# LED_SHEET.net
KiCad netlist of a schematic drawn in Altium Designer
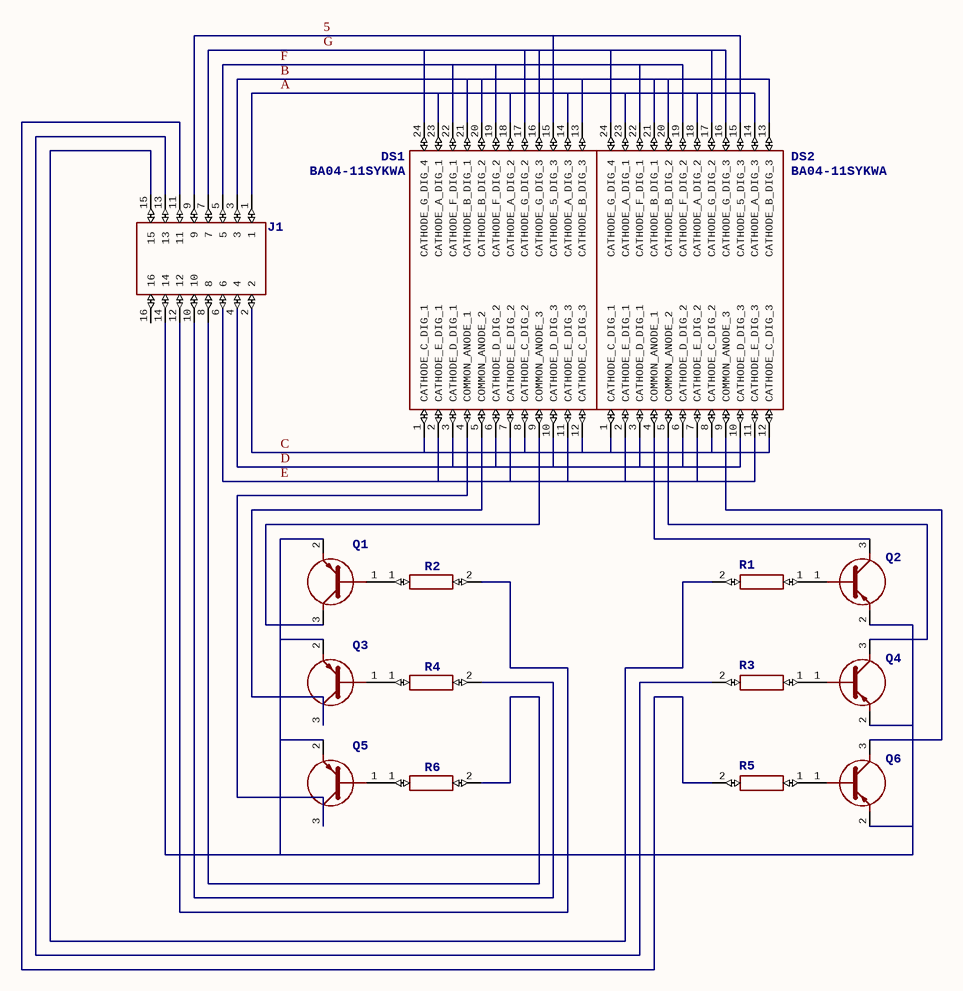
[diagram p0: LED_SHEET.SchDoc]

(export (version "E")
  (design (tool "Eeschema 10.0.6"))
  (components
    (comp (ref "DS1")
      (value "BA04-11SYKWA")
      (footprint "DIPS1270W70P254L3020H725Q24N")
      (libsource (lib "877-0833") (part "BA04-11SYKWA"))
    )
    (comp (ref "DS2")
      (value "BA04-11SYKWA")
      (footprint "DIPS1270W70P254L3020H725Q24N")
      (libsource (lib "877-0833") (part "BA04-11SYKWA"))
    )
    (comp (ref "J1")
      (value "~")
      (footprint "SHDR16W64P254_2X8_2790X860X930")
      (fields (field (name "MANUFACTURER_PART_NUMBER") "6257268"))
      (libsource (lib "625-7268") (part "6257268"))
    )
    (comp (ref "Q1")
      (value "~")
      (footprint "SOT95P230X110-3N")
      (fields
        (field (name "MANUFACTURER_PART_NUMBER") "BC857,215")
        (field (name "MOUSER_PART_NUMBER") "771-BC857215")
      )
      (libsource (lib "484-5100") (part "BC857,215"))
    )
    (comp (ref "Q2")
      (value "~")
      (footprint "SOT95P230X110-3N")
      (fields
        (field (name "MANUFACTURER_PART_NUMBER") "BC857,215")
        (field (name "MOUSER_PART_NUMBER") "771-BC857215")
      )
      (libsource (lib "484-5100") (part "BC857,215"))
    )
    (comp (ref "Q3")
      (value "~")
      (footprint "SOT95P230X110-3N")
      (fields
        (field (name "MANUFACTURER_PART_NUMBER") "BC857,215")
        (field (name "MOUSER_PART_NUMBER") "771-BC857215")
      )
      (libsource (lib "484-5100") (part "BC857,215"))
    )
    (comp (ref "Q4")
      (value "~")
      (footprint "SOT95P230X110-3N")
      (fields
        (field (name "MANUFACTURER_PART_NUMBER") "BC857,215")
        (field (name "MOUSER_PART_NUMBER") "771-BC857215")
      )
      (libsource (lib "484-5100") (part "BC857,215"))
    )
    (comp (ref "Q5")
      (value "~")
      (footprint "SOT95P230X110-3N")
      (fields
        (field (name "MANUFACTURER_PART_NUMBER") "BC857,215")
        (field (name "MOUSER_PART_NUMBER") "771-BC857215")
      )
      (libsource (lib "484-5100") (part "BC857,215"))
    )
    (comp (ref "Q6")
      (value "~")
      (footprint "SOT95P230X110-3N")
      (fields
        (field (name "MANUFACTURER_PART_NUMBER") "BC857,215")
        (field (name "MOUSER_PART_NUMBER") "771-BC857215")
      )
      (libsource (lib "484-5100") (part "BC857,215"))
    )
    (comp (ref "R1")
      (value "~")
      (footprint "RESC3116X65N")
      (fields
        (field (name "MANUFACTURER_PART_NUMBER") "CRG1206F150R")
        (field (name "MOUSER_PART_NUMBER") "279-CRG1206F150R")
      )
      (libsource (lib "223-2142") (part "CRG1206F150R"))
    )
    (comp (ref "R2")
      (value "~")
      (footprint "RESC3116X65N")
      (fields
        (field (name "MANUFACTURER_PART_NUMBER") "CRG1206F150R")
        (field (name "MOUSER_PART_NUMBER") "279-CRG1206F150R")
      )
      (libsource (lib "223-2142") (part "CRG1206F150R"))
    )
    (comp (ref "R3")
      (value "~")
      (footprint "RESC3116X65N")
      (fields
        (field (name "MANUFACTURER_PART_NUMBER") "CRG1206F150R")
        (field (name "MOUSER_PART_NUMBER") "279-CRG1206F150R")
      )
      (libsource (lib "223-2142") (part "CRG1206F150R"))
    )
    (comp (ref "R4")
      (value "~")
      (footprint "RESC3116X65N")
      (fields
        (field (name "MANUFACTURER_PART_NUMBER") "CRG1206F150R")
        (field (name "MOUSER_PART_NUMBER") "279-CRG1206F150R")
      )
      (libsource (lib "223-2142") (part "CRG1206F150R"))
    )
    (comp (ref "R5")
      (value "~")
      (footprint "RESC3116X65N")
      (fields
        (field (name "MANUFACTURER_PART_NUMBER") "CRG1206F150R")
        (field (name "MOUSER_PART_NUMBER") "279-CRG1206F150R")
      )
      (libsource (lib "223-2142") (part "CRG1206F150R"))
    )
    (comp (ref "R6")
      (value "~")
      (footprint "RESC3116X65N")
      (fields
        (field (name "MANUFACTURER_PART_NUMBER") "CRG1206F150R")
        (field (name "MOUSER_PART_NUMBER") "279-CRG1206F150R")
      )
      (libsource (lib "223-2142") (part "CRG1206F150R"))
    )
  )
  (nets
    (net (code "1") (name "/5") (class "Default")
      (node (ref "DS1") (pin "15") (pinfunction "CATHODE_5_DIG_3_15") (pintype "bidirectional"))
      (node (ref "DS2") (pin "15") (pinfunction "CATHODE_5_DIG_3_15") (pintype "bidirectional"))
      (node (ref "J1") (pin "9") (pinfunction "9_9") (pintype "bidirectional"))
    )
    (net (code "2") (name "/A") (class "Default")
      (node (ref "DS1") (pin "14") (pinfunction "CATHODE_A_DIG_3_14") (pintype "bidirectional"))
      (node (ref "DS1") (pin "18") (pinfunction "CATHODE_A_DIG_2_18") (pintype "bidirectional"))
      (node (ref "DS1") (pin "23") (pinfunction "CATHODE_A_DIG_1_23") (pintype "bidirectional"))
      (node (ref "DS2") (pin "14") (pinfunction "CATHODE_A_DIG_3_14") (pintype "bidirectional"))
      (node (ref "DS2") (pin "18") (pinfunction "CATHODE_A_DIG_2_18") (pintype "bidirectional"))
      (node (ref "DS2") (pin "23") (pinfunction "CATHODE_A_DIG_1_23") (pintype "bidirectional"))
      (node (ref "J1") (pin "1") (pinfunction "1_1") (pintype "bidirectional"))
    )
    (net (code "3") (name "/B") (class "Default")
      (node (ref "DS1") (pin "13") (pinfunction "CATHODE_B_DIG_3_13") (pintype "bidirectional"))
      (node (ref "DS1") (pin "20") (pinfunction "CATHODE_B_DIG_2_20") (pintype "bidirectional"))
      (node (ref "DS1") (pin "21") (pinfunction "CATHODE_B_DIG_1_21") (pintype "bidirectional"))
      (node (ref "DS2") (pin "13") (pinfunction "CATHODE_B_DIG_3_13") (pintype "bidirectional"))
      (node (ref "DS2") (pin "20") (pinfunction "CATHODE_B_DIG_2_20") (pintype "bidirectional"))
      (node (ref "DS2") (pin "21") (pinfunction "CATHODE_B_DIG_1_21") (pintype "bidirectional"))
      (node (ref "J1") (pin "3") (pinfunction "3_3") (pintype "bidirectional"))
    )
    (net (code "4") (name "/C") (class "Default")
      (node (ref "DS1") (pin "1") (pinfunction "CATHODE_C_DIG_1_1") (pintype "bidirectional"))
      (node (ref "DS1") (pin "12") (pinfunction "CATHODE_C_DIG_3_12") (pintype "bidirectional"))
      (node (ref "DS1") (pin "8") (pinfunction "CATHODE_C_DIG_2_8") (pintype "bidirectional"))
      (node (ref "DS2") (pin "1") (pinfunction "CATHODE_C_DIG_1_1") (pintype "bidirectional"))
      (node (ref "DS2") (pin "12") (pinfunction "CATHODE_C_DIG_3_12") (pintype "bidirectional"))
      (node (ref "DS2") (pin "8") (pinfunction "CATHODE_C_DIG_2_8") (pintype "bidirectional"))
      (node (ref "J1") (pin "2") (pinfunction "2_2") (pintype "bidirectional"))
    )
    (net (code "5") (name "/D") (class "Default")
      (node (ref "DS1") (pin "10") (pinfunction "CATHODE_D_DIG_3_10") (pintype "bidirectional"))
      (node (ref "DS1") (pin "3") (pinfunction "CATHODE_D_DIG_1_3") (pintype "bidirectional"))
      (node (ref "DS1") (pin "6") (pinfunction "CATHODE_D_DIG_2_6") (pintype "bidirectional"))
      (node (ref "DS2") (pin "10") (pinfunction "CATHODE_D_DIG_3_10") (pintype "bidirectional"))
      (node (ref "DS2") (pin "3") (pinfunction "CATHODE_D_DIG_1_3") (pintype "bidirectional"))
      (node (ref "DS2") (pin "6") (pinfunction "CATHODE_D_DIG_2_6") (pintype "bidirectional"))
      (node (ref "J1") (pin "4") (pinfunction "4_4") (pintype "bidirectional"))
    )
    (net (code "6") (name "/E") (class "Default")
      (node (ref "DS1") (pin "11") (pinfunction "CATHODE_E_DIG_3_11") (pintype "bidirectional"))
      (node (ref "DS1") (pin "2") (pinfunction "CATHODE_E_DIG_1_2") (pintype "bidirectional"))
      (node (ref "DS1") (pin "7") (pinfunction "CATHODE_E_DIG_2_7") (pintype "bidirectional"))
      (node (ref "DS2") (pin "11") (pinfunction "CATHODE_E_DIG_3_11") (pintype "bidirectional"))
      (node (ref "DS2") (pin "2") (pinfunction "CATHODE_E_DIG_1_2") (pintype "bidirectional"))
      (node (ref "DS2") (pin "7") (pinfunction "CATHODE_E_DIG_2_7") (pintype "bidirectional"))
      (node (ref "J1") (pin "6") (pinfunction "6_6") (pintype "bidirectional"))
    )
    (net (code "7") (name "/F") (class "Default")
      (node (ref "DS1") (pin "19") (pinfunction "CATHODE_F_DIG_2_19") (pintype "bidirectional"))
      (node (ref "DS1") (pin "22") (pinfunction "CATHODE_F_DIG_1_22") (pintype "bidirectional"))
      (node (ref "DS2") (pin "19") (pinfunction "CATHODE_F_DIG_2_19") (pintype "bidirectional"))
      (node (ref "DS2") (pin "22") (pinfunction "CATHODE_F_DIG_1_22") (pintype "bidirectional"))
      (node (ref "J1") (pin "5") (pinfunction "5_5") (pintype "bidirectional"))
    )
    (net (code "8") (name "/G") (class "Default")
      (node (ref "DS1") (pin "16") (pinfunction "CATHODE_G_DIG_3_16") (pintype "bidirectional"))
      (node (ref "DS1") (pin "17") (pinfunction "CATHODE_G_DIG_2_17") (pintype "bidirectional"))
      (node (ref "DS1") (pin "24") (pinfunction "CATHODE_G_DIG_4_24") (pintype "bidirectional"))
      (node (ref "DS2") (pin "16") (pinfunction "CATHODE_G_DIG_3_16") (pintype "bidirectional"))
      (node (ref "DS2") (pin "17") (pinfunction "CATHODE_G_DIG_2_17") (pintype "bidirectional"))
      (node (ref "DS2") (pin "24") (pinfunction "CATHODE_G_DIG_4_24") (pintype "bidirectional"))
      (node (ref "J1") (pin "7") (pinfunction "7_7") (pintype "bidirectional"))
    )
    (net (code "9") (name "Net-(DS1-COMMON_ANODE_1)") (class "Default")
      (node (ref "DS1") (pin "4") (pinfunction "COMMON_ANODE_1_4") (pintype "bidirectional"))
      (node (ref "Q5") (pin "3") (pinfunction "C_3") (pintype "bidirectional"))
    )
    (net (code "10") (name "Net-(DS1-COMMON_ANODE_2)") (class "Default")
      (node (ref "DS1") (pin "5") (pinfunction "COMMON_ANODE_2_5") (pintype "bidirectional"))
      (node (ref "Q3") (pin "3") (pinfunction "C_3") (pintype "bidirectional"))
    )
    (net (code "11") (name "Net-(DS1-COMMON_ANODE_3)") (class "Default")
      (node (ref "DS1") (pin "9") (pinfunction "COMMON_ANODE_3_9") (pintype "bidirectional"))
      (node (ref "Q1") (pin "3") (pinfunction "C_3") (pintype "bidirectional"))
    )
    (net (code "12") (name "Net-(DS2-COMMON_ANODE_1)") (class "Default")
      (node (ref "DS2") (pin "4") (pinfunction "COMMON_ANODE_1_4") (pintype "bidirectional"))
      (node (ref "Q2") (pin "3") (pinfunction "C_3") (pintype "bidirectional"))
    )
    (net (code "13") (name "Net-(DS2-COMMON_ANODE_2)") (class "Default")
      (node (ref "DS2") (pin "5") (pinfunction "COMMON_ANODE_2_5") (pintype "bidirectional"))
      (node (ref "Q4") (pin "3") (pinfunction "C_3") (pintype "bidirectional"))
    )
    (net (code "14") (name "Net-(DS2-COMMON_ANODE_3)") (class "Default")
      (node (ref "DS2") (pin "9") (pinfunction "COMMON_ANODE_3_9") (pintype "bidirectional"))
      (node (ref "Q6") (pin "3") (pinfunction "C_3") (pintype "bidirectional"))
    )
    (net (code "15") (name "Net-(J1-Pad8)") (class "Default")
      (node (ref "J1") (pin "8") (pinfunction "8_8") (pintype "bidirectional"))
      (node (ref "R6") (pin "2") (pinfunction "2_2") (pintype "bidirectional"))
    )
    (net (code "16") (name "Net-(J1-Pad10)") (class "Default")
      (node (ref "J1") (pin "10") (pinfunction "10_10") (pintype "bidirectional"))
      (node (ref "R4") (pin "2") (pinfunction "2_2") (pintype "bidirectional"))
    )
    (net (code "17") (name "Net-(J1-Pad11)") (class "Default")
      (node (ref "J1") (pin "11") (pinfunction "11_11") (pintype "bidirectional"))
      (node (ref "R5") (pin "2") (pinfunction "2_2") (pintype "bidirectional"))
    )
    (net (code "18") (name "Net-(J1-Pad12)") (class "Default")
      (node (ref "J1") (pin "12") (pinfunction "12_12") (pintype "bidirectional"))
      (node (ref "R2") (pin "2") (pinfunction "2_2") (pintype "bidirectional"))
    )
    (net (code "19") (name "Net-(J1-Pad13)") (class "Default")
      (node (ref "J1") (pin "13") (pinfunction "13_13") (pintype "bidirectional"))
      (node (ref "R3") (pin "2") (pinfunction "2_2") (pintype "bidirectional"))
    )
    (net (code "20") (name "Net-(J1-Pad15)") (class "Default")
      (node (ref "J1") (pin "15") (pinfunction "15_15") (pintype "bidirectional"))
      (node (ref "R1") (pin "2") (pinfunction "2_2") (pintype "bidirectional"))
    )
    (net (code "21") (name "Net-(Q1-B)") (class "Default")
      (node (ref "Q1") (pin "1") (pinfunction "B_1") (pintype "bidirectional"))
      (node (ref "R2") (pin "1") (pinfunction "1_1") (pintype "bidirectional"))
    )
    (net (code "22") (name "Net-(Q1-E)") (class "Default")
      (node (ref "J1") (pin "14") (pinfunction "14_14") (pintype "bidirectional"))
      (node (ref "Q1") (pin "2") (pinfunction "E_2") (pintype "bidirectional"))
      (node (ref "Q2") (pin "2") (pinfunction "E_2") (pintype "bidirectional"))
      (node (ref "Q3") (pin "2") (pinfunction "E_2") (pintype "bidirectional"))
      (node (ref "Q4") (pin "2") (pinfunction "E_2") (pintype "bidirectional"))
      (node (ref "Q5") (pin "2") (pinfunction "E_2") (pintype "bidirectional"))
      (node (ref "Q6") (pin "2") (pinfunction "E_2") (pintype "bidirectional"))
    )
    (net (code "23") (name "Net-(Q2-B)") (class "Default")
      (node (ref "Q2") (pin "1") (pinfunction "B_1") (pintype "bidirectional"))
      (node (ref "R1") (pin "1") (pinfunction "1_1") (pintype "bidirectional"))
    )
    (net (code "24") (name "Net-(Q3-B)") (class "Default")
      (node (ref "Q3") (pin "1") (pinfunction "B_1") (pintype "bidirectional"))
      (node (ref "R4") (pin "1") (pinfunction "1_1") (pintype "bidirectional"))
    )
    (net (code "25") (name "Net-(Q4-B)") (class "Default")
      (node (ref "Q4") (pin "1") (pinfunction "B_1") (pintype "bidirectional"))
      (node (ref "R3") (pin "1") (pinfunction "1_1") (pintype "bidirectional"))
    )
    (net (code "26") (name "Net-(Q5-B)") (class "Default")
      (node (ref "Q5") (pin "1") (pinfunction "B_1") (pintype "bidirectional"))
      (node (ref "R6") (pin "1") (pinfunction "1_1") (pintype "bidirectional"))
    )
    (net (code "27") (name "Net-(Q6-B)") (class "Default")
      (node (ref "Q6") (pin "1") (pinfunction "B_1") (pintype "bidirectional"))
      (node (ref "R5") (pin "1") (pinfunction "1_1") (pintype "bidirectional"))
    )
    (net (code "28") (name "unconnected-(J1-Pad16)") (class "Default")
      (node (ref "J1") (pin "16") (pinfunction "16_16") (pintype "bidirectional"))
    )
  )
)
